# ProProject___2024-03-21.net
KiCad netlist of a schematic drawn in EasyEDA Pro
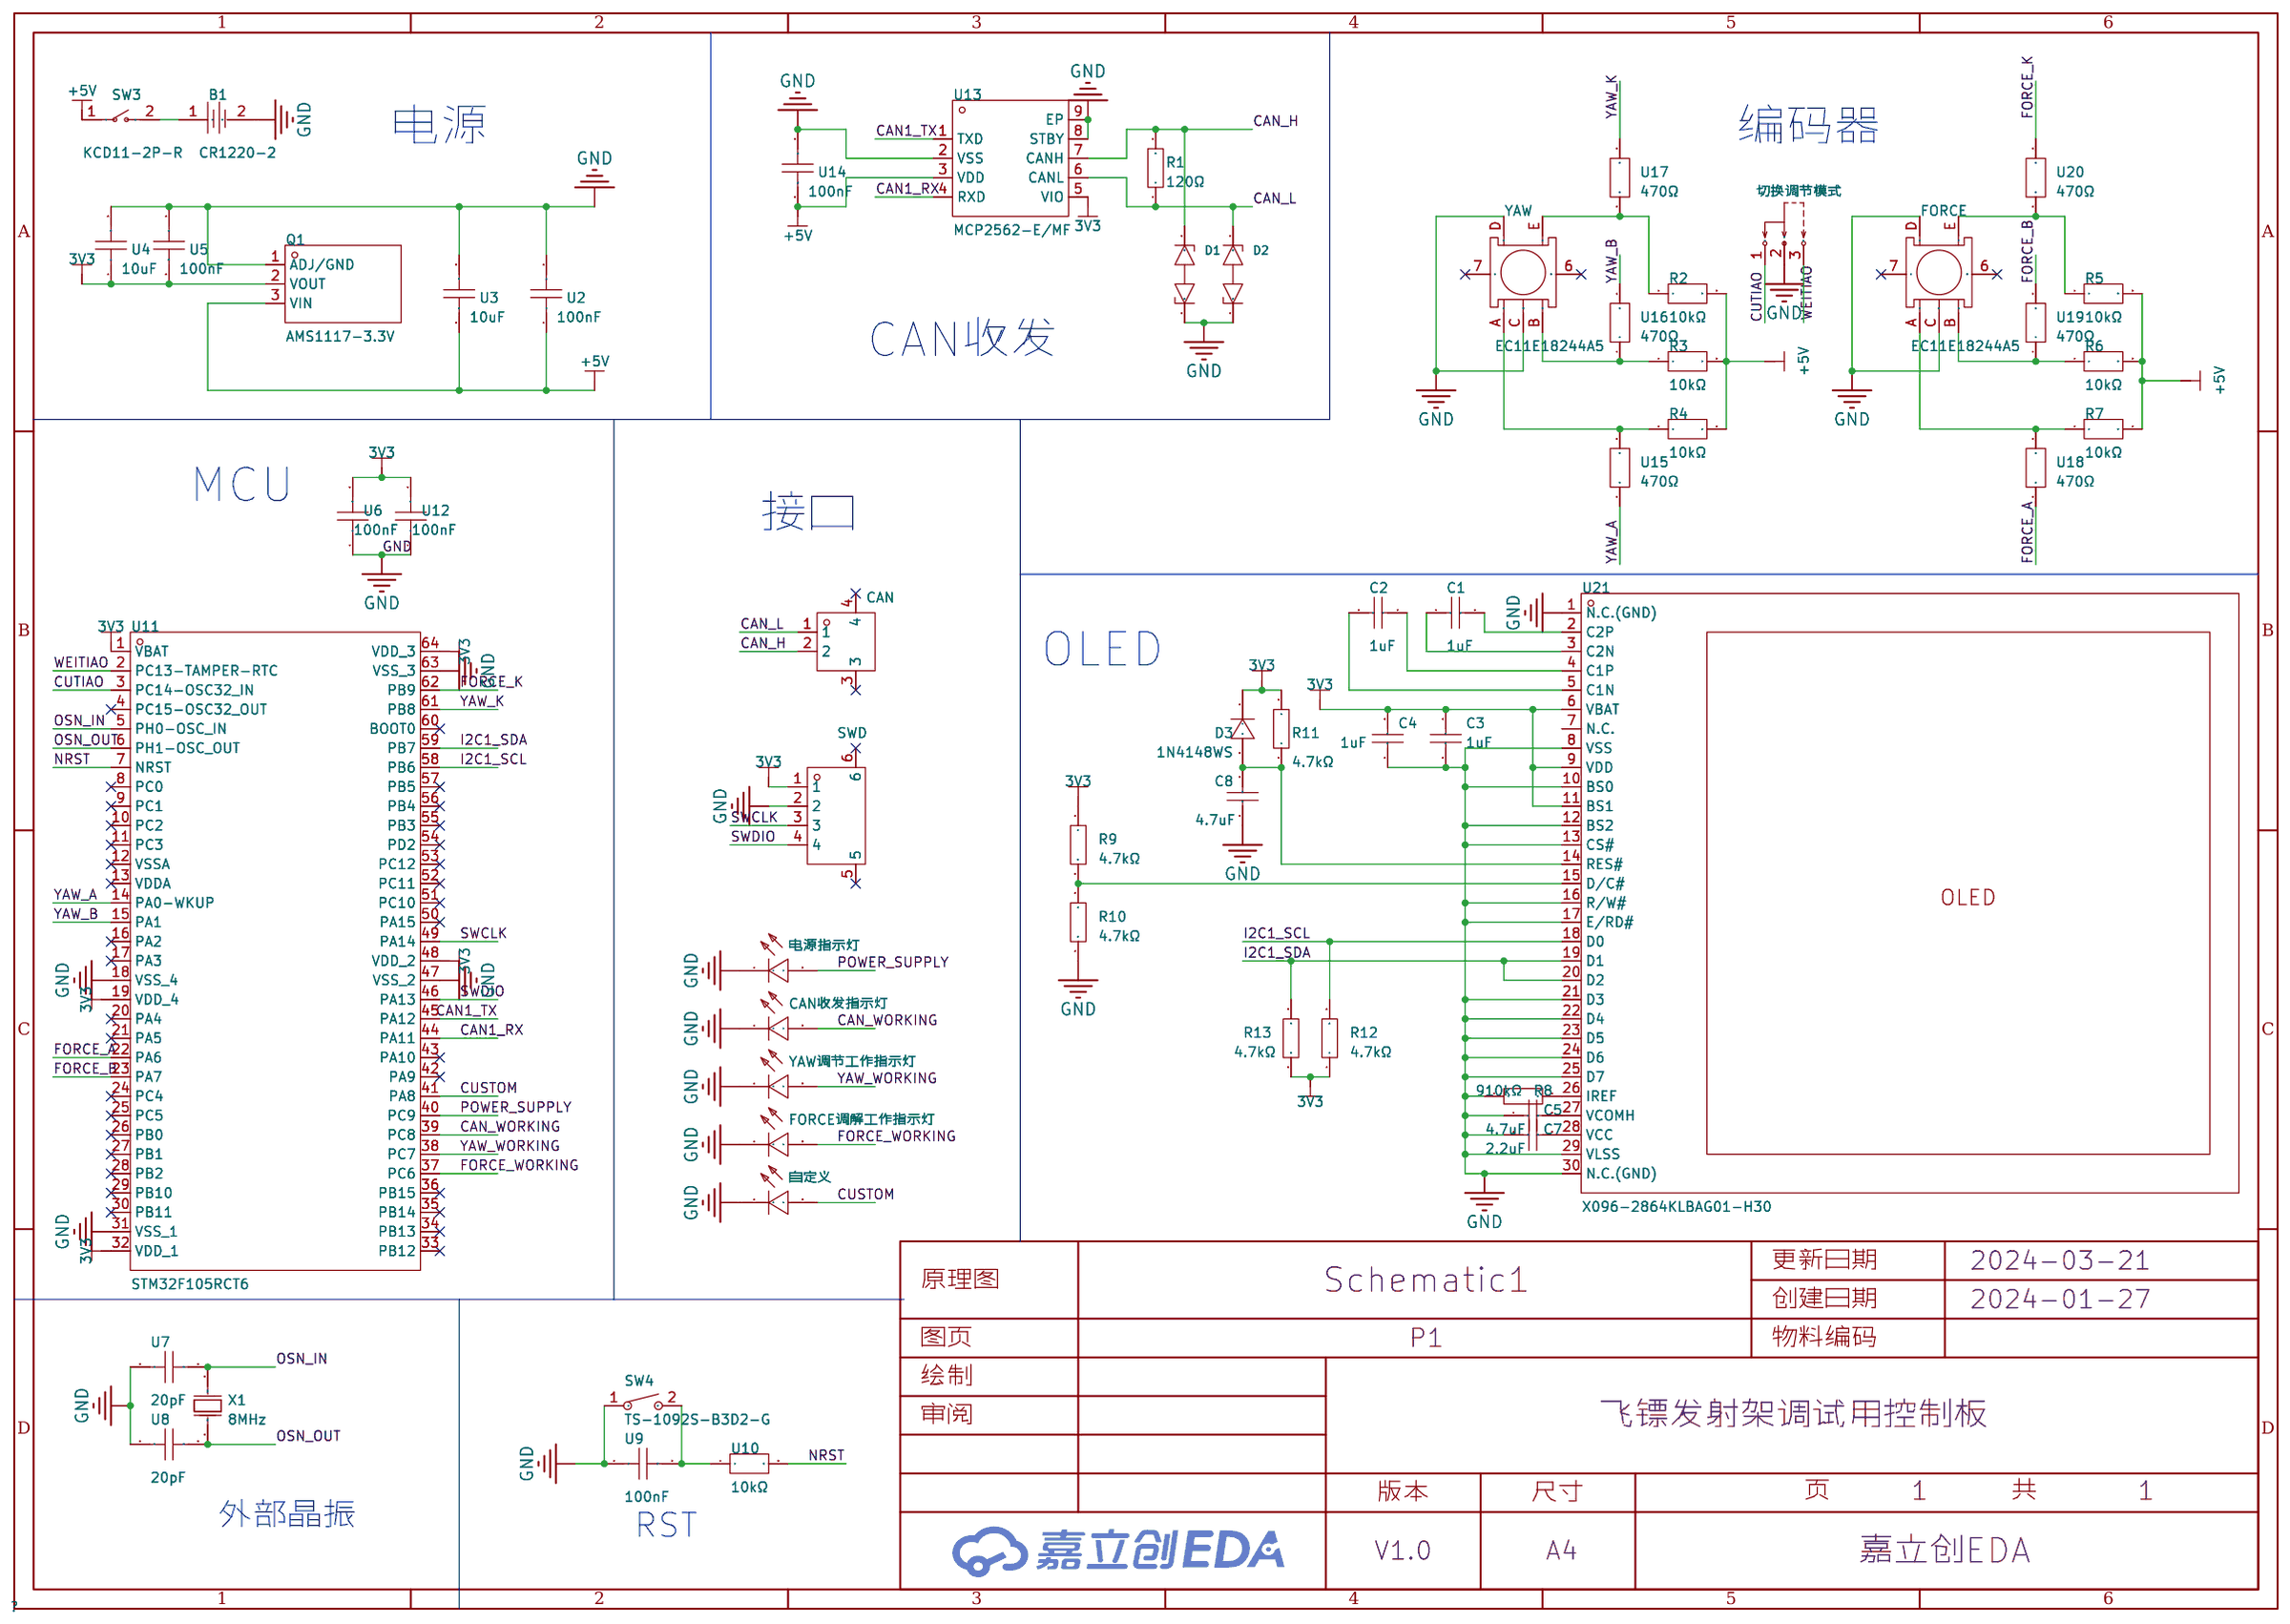
[diagram p0: schematic sheet]

(export (version "E")
  (design (tool "Eeschema 10.0.6"))
  (components
    (comp (ref "B1")
      (value "CR1220-2")
      (footprint "easyedapro:BAT-SMD_CR1220-2")
      (description "连接器类型:电池底座;适用电池规格:CR1220;工作温度范围:-;")
      (fields (field (name "Manufacturer") "Q&J"))
      (libsource (lib "easyedapro") (part "CR1220-2"))
    )
    (comp (ref "C1")
      (value "1uF")
      (footprint "easyedapro:C0603")
      (description "容值:1uF;精度:±10%;额定电压:25V;材质(温度系数):X7R;")
      (fields (field (name "Manufacturer Part") "0603B105K250NT") (field (name "Manufacturer") "FH(风华)"))
      (libsource (lib "easyedapro") (part "0603B105K250NT"))
    )
    (comp (ref "C2")
      (value "1uF")
      (footprint "easyedapro:C0603")
      (description "容值:1uF;精度:±10%;额定电压:25V;材质(温度系数):X7R;")
      (fields (field (name "Manufacturer Part") "0603B105K250NT") (field (name "Manufacturer") "FH(风华)"))
      (libsource (lib "easyedapro") (part "0603B105K250NT"))
    )
    (comp (ref "C3")
      (value "1uF")
      (footprint "easyedapro:C0603")
      (description "容值:1uF;精度:±10%;额定电压:25V;材质(温度系数):X7R;")
      (fields (field (name "Manufacturer Part") "0603B105K250NT") (field (name "Manufacturer") "FH(风华)"))
      (libsource (lib "easyedapro") (part "0603B105K250NT"))
    )
    (comp (ref "C4")
      (value "1uF")
      (footprint "easyedapro:C0603")
      (description "容值:1uF;精度:±10%;额定电压:25V;材质(温度系数):X7R;")
      (fields (field (name "Manufacturer Part") "0603B105K250NT") (field (name "Manufacturer") "FH(风华)"))
      (libsource (lib "easyedapro") (part "0603B105K250NT"))
    )
    (comp (ref "C5")
      (value "4.7uF")
      (footprint "easyedapro:C0603")
      (description "容值:4.7uF;精度:±10%;额定电压:16V;材质(温度系数):X5R;")
      (fields
        (field (name "Manufacturer Part") "CL10A475KO8NNNC")
        (field (name "Manufacturer") "SAMSUNG(三星)")
      )
      (libsource (lib "easyedapro") (part "CL10A475KO8NNNC"))
    )
    (comp (ref "C7")
      (value "2.2uF")
      (footprint "easyedapro:C0603")
      (description "容值:2.2uF;精度:±10%;额定电压:16V;材质(温度系数):X5R;")
      (fields
        (field (name "Manufacturer Part") "CL10A225KO8NNNC")
        (field (name "Manufacturer") "SAMSUNG(三星)")
      )
      (libsource (lib "easyedapro") (part "CL10A225KO8NNNC"))
    )
    (comp (ref "C8")
      (value "4.7uF")
      (footprint "easyedapro:C0603")
      (description "容值:4.7uF;精度:±10%;额定电压:16V;材质(温度系数):X5R;")
      (fields
        (field (name "Manufacturer Part") "CL10A475KO8NNNC")
        (field (name "Manufacturer") "SAMSUNG(三星)")
      )
      (libsource (lib "easyedapro") (part "CL10A475KO8NNNC"))
    )
    (comp (ref "CAN")
      (value "WAFER-GH1.25-2PLB")
      (footprint "easyedapro:CONN-TH_2P-P1.25_XUNPU_WAFER-GH1.25-2PLB")
      (description "插针结构:1x2P;间距:1.25mm;安装方式:立贴;参考系列:GH;总PIN数:2P;排数:1;每排PIN数:2;额定电流:1A;工作温度范围:-25°C~+85°C;")
      (fields (field (name "Manufacturer") "XUNPU(讯普)"))
      (libsource (lib "easyedapro") (part "WAFER-GH1.25-2PLB"))
    )
    (comp (ref "CAN收发指示灯")
      (value "NCD0603R1")
      (footprint "easyedapro:LED0603-RD_RED")
      (fields (field (name "Manufacturer") "国星光电"))
      (libsource (lib "easyedapro") (part "FC-DA1608HRK-620D"))
    )
    (comp (ref "D1")
      (value "PESD5V0S1BA,115")
      (footprint "easyedapro:SOD-323_L1.7-W1.3-LS2.5-BI")
      (description "极性:双向;反向截止电压(Vrwm):5V;最大钳位电压:14V;峰值脉冲电流(Ipp)@10/1000us:12A;峰值脉冲功率(Ppp)@10/1000us:130W;击穿电压:5.5V;")
      (fields (field (name "Manufacturer") "Nexperia(安世)"))
      (libsource (lib "easyedapro") (part "PESD5V0S1BA,115"))
    )
    (comp (ref "D2")
      (value "PESD5V0S1BA,115")
      (footprint "easyedapro:SOD-323_L1.7-W1.3-LS2.5-BI")
      (description "极性:双向;反向截止电压(Vrwm):5V;最大钳位电压:14V;峰值脉冲电流(Ipp)@10/1000us:12A;峰值脉冲功率(Ppp)@10/1000us:130W;击穿电压:5.5V;")
      (fields (field (name "Manufacturer") "Nexperia(安世)"))
      (libsource (lib "easyedapro") (part "PESD5V0S1BA,115"))
    )
    (comp (ref "D3")
      (value "1N4148WS")
      (footprint "easyedapro:SOD-323_L1.8-W1.3-LS2.5-RD")
      (description "二极管配置:独立式;正向压降(Vf):1.25V@150mA;直流反向耐压(Vr):100V;平均整流电流(Io):150mA;功率:200mW;反向恢复时间(trr):4ns;")
      (fields (field (name "Manufacturer") "CJ(江苏长电/长晶)"))
      (libsource (lib "easyedapro") (part "1N4148WS T4"))
    )
    (comp (ref "FORCE")
      (value "EC11E18244A5")
      (footprint "easyedapro:SW-TH_EC11E18244A5")
      (fields (field (name "Manufacturer") "ALPSALPINE(阿尔卑斯阿尔派)"))
      (libsource (lib "easyedapro") (part "EC11E18244A5"))
    )
    (comp (ref "FORCE调解工作指示灯")
      (value "NCD0603R1")
      (footprint "easyedapro:LED0603-RD_RED")
      (fields (field (name "Manufacturer") "国星光电"))
      (libsource (lib "easyedapro") (part "FC-DA1608HRK-620D"))
    )
    (comp (ref "Q1")
      (value "AMS1117-3.3V")
      (footprint "easyedapro:SOT-89-3_L4.5-W2.5-P1.50-LS4.2-BR")
      (description "输出类型:固定;最大输入电压:18V;输出电压:3.3V;最大输出电流:1A;输出极性:正极;")
      (fields (field (name "Manufacturer") "MSKSEMI(美森科)"))
      (libsource (lib "easyedapro") (part "AMS1117-3.3V_C5120796"))
    )
    (comp (ref "R1")
      (value "120Ω")
      (footprint "easyedapro:R0603")
      (description "电阻类型:厚膜电阻;阻值:120Ω;精度:±1%;功率:100mW;最大工作电压:75V;温度系数:±100ppm/°C;")
      (fields
        (field (name "Manufacturer Part") "0603WAF1200T5E")
        (field (name "Manufacturer") "UNI-ROYAL(厚声)")
      )
      (libsource (lib "easyedapro") (part "0603WAF1200T5E"))
    )
    (comp (ref "R2")
      (value "10kΩ")
      (footprint "easyedapro:R0603")
      (description "电阻类型:薄膜电阻;阻值:10kΩ;精度:±0.01%;功率:150mW;温度系数:±5ppm/°C;")
      (fields
        (field (name "Manufacturer Part") "PLT0603Z1002LBTS")
        (field (name "Manufacturer") "VISHAY(威世)")
      )
      (libsource (lib "easyedapro") (part "PLT0603Z1002LBTS"))
    )
    (comp (ref "R3")
      (value "10kΩ")
      (footprint "easyedapro:R0603")
      (description "电阻类型:薄膜电阻;阻值:10kΩ;精度:±0.01%;功率:150mW;温度系数:±5ppm/°C;")
      (fields
        (field (name "Manufacturer Part") "PLT0603Z1002LBTS")
        (field (name "Manufacturer") "VISHAY(威世)")
      )
      (libsource (lib "easyedapro") (part "PLT0603Z1002LBTS"))
    )
    (comp (ref "R4")
      (value "10kΩ")
      (footprint "easyedapro:R0603")
      (description "电阻类型:薄膜电阻;阻值:10kΩ;精度:±0.01%;功率:150mW;温度系数:±5ppm/°C;")
      (fields
        (field (name "Manufacturer Part") "PLT0603Z1002LBTS")
        (field (name "Manufacturer") "VISHAY(威世)")
      )
      (libsource (lib "easyedapro") (part "PLT0603Z1002LBTS"))
    )
    (comp (ref "R5")
      (value "10kΩ")
      (footprint "easyedapro:R0603")
      (description "电阻类型:薄膜电阻;阻值:10kΩ;精度:±0.01%;功率:150mW;温度系数:±5ppm/°C;")
      (fields
        (field (name "Manufacturer Part") "PLT0603Z1002LBTS")
        (field (name "Manufacturer") "VISHAY(威世)")
      )
      (libsource (lib "easyedapro") (part "PLT0603Z1002LBTS"))
    )
    (comp (ref "R6")
      (value "10kΩ")
      (footprint "easyedapro:R0603")
      (description "电阻类型:薄膜电阻;阻值:10kΩ;精度:±0.01%;功率:150mW;温度系数:±5ppm/°C;")
      (fields
        (field (name "Manufacturer Part") "PLT0603Z1002LBTS")
        (field (name "Manufacturer") "VISHAY(威世)")
      )
      (libsource (lib "easyedapro") (part "PLT0603Z1002LBTS"))
    )
    (comp (ref "R7")
      (value "10kΩ")
      (footprint "easyedapro:R0603")
      (description "电阻类型:薄膜电阻;阻值:10kΩ;精度:±0.01%;功率:150mW;温度系数:±5ppm/°C;")
      (fields
        (field (name "Manufacturer Part") "PLT0603Z1002LBTS")
        (field (name "Manufacturer") "VISHAY(威世)")
      )
      (libsource (lib "easyedapro") (part "PLT0603Z1002LBTS"))
    )
    (comp (ref "R8")
      (value "910kΩ")
      (footprint "easyedapro:R0603")
      (description "电阻类型:厚膜电阻;阻值:910kΩ;精度:±1%;功率:100mW;最大工作电压:75V;温度系数:±100ppm/°C;")
      (fields
        (field (name "Manufacturer Part") "0603WAF9103T5E")
        (field (name "Manufacturer") "UNI-ROYAL(厚声)")
      )
      (libsource (lib "easyedapro") (part "0603WAF9103T5E"))
    )
    (comp (ref "R9")
      (value "4.7kΩ")
      (footprint "easyedapro:R0603")
      (description "电阻类型:厚膜电阻;阻值:4.7kΩ;精度:±1%;功率:100mW;最大工作电压:75V;温度系数:±100ppm/°C;")
      (fields
        (field (name "Manufacturer Part") "0603WAF4701T5E")
        (field (name "Manufacturer") "UNI-ROYAL(厚声)")
      )
      (libsource (lib "easyedapro") (part "0603WAF4701T5E"))
    )
    (comp (ref "R10")
      (value "4.7kΩ")
      (footprint "easyedapro:R0603")
      (description "电阻类型:厚膜电阻;阻值:4.7kΩ;精度:±1%;功率:100mW;最大工作电压:75V;温度系数:±100ppm/°C;")
      (fields
        (field (name "Manufacturer Part") "0603WAF4701T5E")
        (field (name "Manufacturer") "UNI-ROYAL(厚声)")
      )
      (libsource (lib "easyedapro") (part "0603WAF4701T5E"))
    )
    (comp (ref "R11")
      (value "4.7kΩ")
      (footprint "easyedapro:R0603")
      (description "电阻类型:厚膜电阻;阻值:4.7kΩ;精度:±1%;功率:100mW;最大工作电压:75V;温度系数:±100ppm/°C;")
      (fields
        (field (name "Manufacturer Part") "0603WAF4701T5E")
        (field (name "Manufacturer") "UNI-ROYAL(厚声)")
      )
      (libsource (lib "easyedapro") (part "0603WAF4701T5E"))
    )
    (comp (ref "R12")
      (value "4.7kΩ")
      (footprint "easyedapro:R0603")
      (description "电阻类型:厚膜电阻;阻值:4.7kΩ;精度:±1%;功率:100mW;最大工作电压:75V;温度系数:±100ppm/°C;")
      (fields
        (field (name "Manufacturer Part") "0603WAF4701T5E")
        (field (name "Manufacturer") "UNI-ROYAL(厚声)")
      )
      (libsource (lib "easyedapro") (part "0603WAF4701T5E"))
    )
    (comp (ref "R13")
      (value "4.7kΩ")
      (footprint "easyedapro:R0603")
      (description "电阻类型:厚膜电阻;阻值:4.7kΩ;精度:±1%;功率:100mW;最大工作电压:75V;温度系数:±100ppm/°C;")
      (fields
        (field (name "Manufacturer Part") "0603WAF4701T5E")
        (field (name "Manufacturer") "UNI-ROYAL(厚声)")
      )
      (libsource (lib "easyedapro") (part "0603WAF4701T5E"))
    )
    (comp (ref "SW3")
      (value "KCD11-2P-R")
      (footprint "easyedapro:SW-TH_2P-L15.0-W10.5-P5.00_KCD11-2P-R")
      (description "带灯:无;引脚样式:焊片;额定电流:3A;额定电压(AC):250V;额定电压(DC):-;电路结构:单刀单掷;机械寿命:1万次;")
      (fields (field (name "Manufacturer") "SHOU HAN(首韩)"))
      (libsource (lib "easyedapro") (part "KCD11-2P-R"))
    )
    (comp (ref "SW4")
      (value "TS-1092S-B3D2-G")
      (footprint "easyedapro:SW-SMD_L6.1-W3.6-LS7.9")
      (description "电路结构:单刀单掷;按钮形状:矩形按钮;作用力:250gf;安装方式:立贴;开关长度:6.1mm;开关宽度:3.6mm;开关高度:2.5mm;带支架:不带;机械寿命:-;")
      (fields (field (name "Manufacturer") "Yuandi(元迪)"))
      (libsource (lib "easyedapro") (part "TS-1092S-B3D2-G"))
    )
    (comp (ref "SWD")
      (value "WAFER-MX1.25-4PWB")
      (footprint "easyedapro:CONN-SMD_4P-P1.25_WAFER-MX1.25-4PWB")
      (description "插针结构:1x4P;间距:1.25mm;安装方式:卧贴;总PIN数:4P;排数:1;每排PIN数:4;额定电流:1A;工作温度范围:-25°C~+85°C;")
      (fields (field (name "Manufacturer") "XUNPU(讯普)"))
      (libsource (lib "easyedapro") (part "WAFER-MX1.25-4PWB"))
    )
    (comp (ref "U2")
      (value "100nF")
      (footprint "easyedapro:C0603")
      (description "容值:100nF;精度:±20%;额定电压:16V;材质(温度系数):X7R;")
      (fields
        (field (name "Manufacturer Part") "EMK107B7104MA-T")
        (field (name "Manufacturer") "TAIYO YUDEN(太诱)")
      )
      (libsource (lib "easyedapro") (part "EMK107B7104MA-T"))
    )
    (comp (ref "U3")
      (value "10uF")
      (footprint "easyedapro:C0603")
      (description "容值:10uF;精度:±20%;额定电压:6.3V;材质(温度系数):X5R;")
      (fields
        (field (name "Manufacturer Part") "GRM188R60J106ME84D")
        (field (name "Manufacturer") "muRata(村田)")
      )
      (libsource (lib "easyedapro") (part "GRM188R60J106ME84D"))
    )
    (comp (ref "U4")
      (value "10uF")
      (footprint "easyedapro:C0603")
      (description "容值:10uF;精度:±20%;额定电压:6.3V;材质(温度系数):X5R;")
      (fields
        (field (name "Manufacturer Part") "GRM188R60J106ME84D")
        (field (name "Manufacturer") "muRata(村田)")
      )
      (libsource (lib "easyedapro") (part "GRM188R60J106ME84D"))
    )
    (comp (ref "U5")
      (value "100nF")
      (footprint "easyedapro:C0603")
      (description "容值:100nF;精度:±20%;额定电压:16V;材质(温度系数):X7R;")
      (fields
        (field (name "Manufacturer Part") "EMK107B7104MA-T")
        (field (name "Manufacturer") "TAIYO YUDEN(太诱)")
      )
      (libsource (lib "easyedapro") (part "EMK107B7104MA-T"))
    )
    (comp (ref "U6")
      (value "100nF")
      (footprint "easyedapro:C0603")
      (description "容值:100nF;精度:±20%;额定电压:16V;材质(温度系数):X7R;")
      (fields
        (field (name "Manufacturer Part") "EMK107B7104MA-T")
        (field (name "Manufacturer") "TAIYO YUDEN(太诱)")
      )
      (libsource (lib "easyedapro") (part "EMK107B7104MA-T"))
    )
    (comp (ref "U7")
      (value "20pF")
      (footprint "easyedapro:C0402")
      (description "容值:20pF;精度:±5%;额定电压:16V;材质(温度系数):C0G;")
      (fields (field (name "Manufacturer Part") "0402YA200JAT2A") (field (name "Manufacturer") "Kyocera AVX"))
      (libsource (lib "easyedapro") (part "0402YA200JAT2A"))
    )
    (comp (ref "U8")
      (value "20pF")
      (footprint "easyedapro:C0402")
      (description "容值:20pF;精度:±5%;额定电压:16V;材质(温度系数):C0G;")
      (fields (field (name "Manufacturer Part") "0402YA200JAT2A") (field (name "Manufacturer") "Kyocera AVX"))
      (libsource (lib "easyedapro") (part "0402YA200JAT2A"))
    )
    (comp (ref "U9")
      (value "100nF")
      (footprint "easyedapro:C0603")
      (description "容值:100nF;精度:±20%;额定电压:16V;材质(温度系数):X7R;")
      (fields
        (field (name "Manufacturer Part") "EMK107B7104MA-T")
        (field (name "Manufacturer") "TAIYO YUDEN(太诱)")
      )
      (libsource (lib "easyedapro") (part "EMK107B7104MA-T"))
    )
    (comp (ref "U10")
      (value "10kΩ")
      (footprint "easyedapro:R0603")
      (description "电阻类型:薄膜电阻;阻值:10kΩ;精度:±0.01%;功率:63mW;温度系数:±5ppm/°C;")
      (fields (field (name "Manufacturer Part") "APC0603T10K0Z") (field (name "Manufacturer") "Ohmite"))
      (libsource (lib "easyedapro") (part "APC0603T10K0Z"))
    )
    (comp (ref "U11")
      (value "STM32F105RCT6")
      (footprint "easyedapro:LQFP-64_L10.0-W10.0-P0.50-LS12.0-BL")
      (description "CPU内核:CM3;程序存储容量:256KB;RAM总容量:64KB;GPIO端口数量:51;工作电压范围:2V~3.6V;CPU最大主频:72MHz;程序存储器类型:FLASH;")
      (fields (field (name "Manufacturer") "ST(意法半导体)"))
      (libsource (lib "easyedapro") (part "STM32F105RCT6"))
    )
    (comp (ref "U12")
      (value "100nF")
      (footprint "easyedapro:C0603")
      (description "容值:100nF;精度:±20%;额定电压:16V;材质(温度系数):X7R;")
      (fields
        (field (name "Manufacturer Part") "EMK107B7104MA-T")
        (field (name "Manufacturer") "TAIYO YUDEN(太诱)")
      )
      (libsource (lib "easyedapro") (part "EMK107B7104MA-T"))
    )
    (comp (ref "U13")
      (value "MCP2562-E/MF")
      (footprint "easyedapro:DFN-8_L3.0-W3.0-P0.65-BL-EP")
      (description "类型:收发器;")
      (fields (field (name "Manufacturer") "MICROCHIP(美国微芯)"))
      (libsource (lib "easyedapro") (part "MCP2562-E/MF"))
    )
    (comp (ref "U14")
      (value "100nF")
      (footprint "easyedapro:C0603")
      (description "容值:100nF;精度:±20%;额定电压:16V;材质(温度系数):X7R;")
      (fields
        (field (name "Manufacturer Part") "EMK107B7104MA-T")
        (field (name "Manufacturer") "TAIYO YUDEN(太诱)")
      )
      (libsource (lib "easyedapro") (part "EMK107B7104MA-T"))
    )
    (comp (ref "U15")
      (value "470Ω")
      (footprint "easyedapro:R0603")
      (description "阻值:470Ω;精度:±5%;功率:-;温度系数:±100ppm/°C;")
      (fields
        (field (name "Manufacturer Part") "SC0603J4700F2BNRH")
        (field (name "Manufacturer") "Sunway(信维通信)")
      )
      (libsource (lib "easyedapro") (part "SC0603J4700F2BNRH"))
    )
    (comp (ref "U16")
      (value "470Ω")
      (footprint "easyedapro:R0603")
      (description "阻值:470Ω;精度:±5%;功率:-;温度系数:±100ppm/°C;")
      (fields
        (field (name "Manufacturer Part") "SC0603J4700F2BNRH")
        (field (name "Manufacturer") "Sunway(信维通信)")
      )
      (libsource (lib "easyedapro") (part "SC0603J4700F2BNRH"))
    )
    (comp (ref "U17")
      (value "470Ω")
      (footprint "easyedapro:R0603")
      (description "阻值:470Ω;精度:±5%;功率:-;温度系数:±100ppm/°C;")
      (fields
        (field (name "Manufacturer Part") "SC0603J4700F2BNRH")
        (field (name "Manufacturer") "Sunway(信维通信)")
      )
      (libsource (lib "easyedapro") (part "SC0603J4700F2BNRH"))
    )
    (comp (ref "U18")
      (value "470Ω")
      (footprint "easyedapro:R0603")
      (description "阻值:470Ω;精度:±5%;功率:-;温度系数:±100ppm/°C;")
      (fields
        (field (name "Manufacturer Part") "SC0603J4700F2BNRH")
        (field (name "Manufacturer") "Sunway(信维通信)")
      )
      (libsource (lib "easyedapro") (part "SC0603J4700F2BNRH"))
    )
    (comp (ref "U19")
      (value "470Ω")
      (footprint "easyedapro:R0603")
      (description "阻值:470Ω;精度:±5%;功率:-;温度系数:±100ppm/°C;")
      (fields
        (field (name "Manufacturer Part") "SC0603J4700F2BNRH")
        (field (name "Manufacturer") "Sunway(信维通信)")
      )
      (libsource (lib "easyedapro") (part "SC0603J4700F2BNRH"))
    )
    (comp (ref "U20")
      (value "470Ω")
      (footprint "easyedapro:R0603")
      (description "阻值:470Ω;精度:±5%;功率:-;温度系数:±100ppm/°C;")
      (fields
        (field (name "Manufacturer Part") "SC0603J4700F2BNRH")
        (field (name "Manufacturer") "Sunway(信维通信)")
      )
      (libsource (lib "easyedapro") (part "SC0603J4700F2BNRH"))
    )
    (comp (ref "U21")
      (value "X096-2864KLBAG01-H30")
      (footprint "easyedapro:OLED-SMD_X096-2864KLBAG01-H30")
      (description "主控芯片:SSD1315;尺寸(inch):0.96;像素分辨率:128x64;")
      (fields (field (name "Manufacturer") "Newvision(新智景)"))
      (libsource (lib "easyedapro") (part "X096-2864KLBAG01-H30"))
    )
    (comp (ref "X1")
      (value "8MHz")
      (footprint "easyedapro:CRYSTAL-SMD_L5.0-W3.2")
      (description "晶振类型:贴片晶振;频率:8MHz;常温频差:±10ppm;外接负载电容:20pF;频率稳定度(全温):±50ppm;")
      (fields (field (name "Manufacturer Part") "X50328MSB2GI") (field (name "Manufacturer") "YXC(扬兴晶振)"))
      (libsource (lib "easyedapro") (part "X50328MSB2GI"))
    )
    (comp (ref "YAW")
      (value "EC11E18244A5")
      (footprint "easyedapro:SW-TH_EC11E18244A5")
      (fields (field (name "Manufacturer") "ALPSALPINE(阿尔卑斯阿尔派)"))
      (libsource (lib "easyedapro") (part "EC11E18244A5"))
    )
    (comp (ref "YAW调节工作指示灯")
      (value "NCD0603R1")
      (footprint "easyedapro:LED0603-RD_RED")
      (fields (field (name "Manufacturer") "国星光电"))
      (libsource (lib "easyedapro") (part "FC-DA1608HRK-620D"))
    )
    (comp (ref "切换调节模式")
      (value "SS12D10G5")
      (footprint "easyedapro:SW-TH_SHOU-HAN_SS12D10G4")
      (description "电路结构:单刀双掷;安装方式:直插;额定电流(DC):2A;额定电压(DC):125V;机械寿命:3千次;")
      (fields (field (name "Manufacturer") "SHOU HAN(首韩)"))
      (libsource (lib "easyedapro") (part "SS12D10G5"))
    )
    (comp (ref "电源指示灯")
      (value "NCD0603R1")
      (footprint "easyedapro:LED0603-RD_RED")
      (fields (field (name "Manufacturer") "国星光电"))
      (libsource (lib "easyedapro") (part "FC-DA1608HRK-620D"))
    )
    (comp (ref "自定义")
      (value "NCD0603R1")
      (footprint "easyedapro:LED0603-RD_RED")
      (fields (field (name "Manufacturer") "国星光电"))
      (libsource (lib "easyedapro") (part "FC-DA1608HRK-620D"))
    )
  )
  (nets
    (net (code "1") (name "+5V") (class "Default")
      (node (ref "Q1") (pin "3") (pinfunction "VIN_3") (pintype "unspecified"))
      (node (ref "R2") (pin "2") (pinfunction "2_2") (pintype "unspecified"))
      (node (ref "R3") (pin "2") (pinfunction "2_2") (pintype "unspecified"))
      (node (ref "R4") (pin "2") (pinfunction "2_2") (pintype "unspecified"))
      (node (ref "R5") (pin "2") (pinfunction "2_2") (pintype "unspecified"))
      (node (ref "R6") (pin "2") (pinfunction "2_2") (pintype "unspecified"))
      (node (ref "R7") (pin "2") (pinfunction "2_2") (pintype "unspecified"))
      (node (ref "SW3") (pin "1") (pinfunction "1_1") (pintype "unspecified"))
      (node (ref "U13") (pin "3") (pinfunction "VDD_3") (pintype "input"))
      (node (ref "U14") (pin "1") (pinfunction "1_1") (pintype "unspecified"))
      (node (ref "U2") (pin "1") (pinfunction "1_1") (pintype "unspecified"))
      (node (ref "U3") (pin "1") (pinfunction "1_1") (pintype "unspecified"))
    )
    (net (code "2") (name "/CAN1_RX") (class "Default")
      (node (ref "U11") (pin "44") (pinfunction "PA11_44") (pintype "unspecified"))
      (node (ref "U13") (pin "4") (pinfunction "RXD_4") (pintype "input"))
    )
    (net (code "3") (name "/CAN1_TX") (class "Default")
      (node (ref "U11") (pin "45") (pinfunction "PA12_45") (pintype "unspecified"))
      (node (ref "U13") (pin "1") (pinfunction "TXD_1") (pintype "input"))
    )
    (net (code "4") (name "/CAN_H") (class "Default")
      (node (ref "CAN") (pin "2") (pinfunction "2_2") (pintype "unspecified"))
      (node (ref "D1") (pin "2") (pinfunction "2_2") (pintype "input"))
      (node (ref "R1") (pin "2") (pinfunction "2_2") (pintype "input"))
      (node (ref "U13") (pin "7") (pinfunction "CANH_7") (pintype "input"))
    )
    (net (code "5") (name "/CAN_L") (class "Default")
      (node (ref "CAN") (pin "1") (pinfunction "1_1") (pintype "unspecified"))
      (node (ref "D2") (pin "2") (pinfunction "2_2") (pintype "input"))
      (node (ref "R1") (pin "1") (pinfunction "1_1") (pintype "input"))
      (node (ref "U13") (pin "6") (pinfunction "CANL_6") (pintype "input"))
    )
    (net (code "6") (name "/CAN_WORKING") (class "Default")
      (node (ref "CAN收发指示灯") (pin "2") (pinfunction "A_2") (pintype "input"))
      (node (ref "U11") (pin "39") (pinfunction "PC8_39") (pintype "unspecified"))
    )
    (net (code "7") (name "/CUSTOM") (class "Default")
      (node (ref "U11") (pin "41") (pinfunction "PA8_41") (pintype "unspecified"))
      (node (ref "自定义") (pin "2") (pinfunction "A_2") (pintype "input"))
    )
    (net (code "8") (name "/CUTIAO") (class "Default")
      (node (ref "U11") (pin "3") (pinfunction "PC14-OSC32_IN_3") (pintype "unspecified"))
      (node (ref "切换调节模式") (pin "1") (pinfunction "1_1") (pintype "unspecified"))
    )
    (net (code "9") (name "/FORCE_A") (class "Default")
      (node (ref "U11") (pin "22") (pinfunction "PA6_22") (pintype "unspecified"))
      (node (ref "U18") (pin "1") (pinfunction "1_1") (pintype "unspecified"))
    )
    (net (code "10") (name "/FORCE_B") (class "Default")
      (node (ref "U11") (pin "23") (pinfunction "PA7_23") (pintype "unspecified"))
      (node (ref "U19") (pin "2") (pinfunction "2_2") (pintype "unspecified"))
    )
    (net (code "11") (name "/FORCE_K") (class "Default")
      (node (ref "U11") (pin "62") (pinfunction "PB9_62") (pintype "unspecified"))
      (node (ref "U20") (pin "2") (pinfunction "2_2") (pintype "unspecified"))
    )
    (net (code "12") (name "/FORCE_WORKING") (class "Default")
      (node (ref "FORCE调解工作指示灯") (pin "2") (pinfunction "A_2") (pintype "input"))
      (node (ref "U11") (pin "37") (pinfunction "PC6_37") (pintype "unspecified"))
    )
    (net (code "13") (name "/I2C1_SCL") (class "Default")
      (node (ref "R12") (pin "2") (pinfunction "2_2") (pintype "input"))
      (node (ref "U11") (pin "58") (pinfunction "PB6_58") (pintype "unspecified"))
      (node (ref "U21") (pin "18") (pinfunction "D0_18") (pintype "unspecified"))
    )
    (net (code "14") (name "/I2C1_SDA") (class "Default")
      (node (ref "R13") (pin "2") (pinfunction "2_2") (pintype "input"))
      (node (ref "U11") (pin "59") (pinfunction "PB7_59") (pintype "unspecified"))
      (node (ref "U21") (pin "19") (pinfunction "D1_19") (pintype "unspecified"))
      (node (ref "U21") (pin "20") (pinfunction "D2_20") (pintype "unspecified"))
    )
    (net (code "15") (name "/NRST") (class "Default")
      (node (ref "U10") (pin "2") (pinfunction "2_2") (pintype "unspecified"))
      (node (ref "U11") (pin "7") (pinfunction "NRST_7") (pintype "unspecified"))
    )
    (net (code "16") (name "/OSN_IN") (class "Default")
      (node (ref "U11") (pin "5") (pinfunction "PH0-OSC_IN_5") (pintype "unspecified"))
      (node (ref "U7") (pin "2") (pinfunction "2_2") (pintype "unspecified"))
      (node (ref "X1") (pin "2") (pinfunction "OSC2_2") (pintype "input"))
    )
    (net (code "17") (name "/OSN_OUT") (class "Default")
      (node (ref "U11") (pin "6") (pinfunction "PH1-OSC_OUT_6") (pintype "unspecified"))
      (node (ref "U8") (pin "2") (pinfunction "2_2") (pintype "unspecified"))
      (node (ref "X1") (pin "1") (pinfunction "OSC1_1") (pintype "input"))
    )
    (net (code "18") (name "/POWER_SUPPLY") (class "Default")
      (node (ref "U11") (pin "40") (pinfunction "PC9_40") (pintype "unspecified"))
      (node (ref "电源指示灯") (pin "2") (pinfunction "A_2") (pintype "input"))
    )
    (net (code "19") (name "/SWCLK") (class "Default")
      (node (ref "SWD") (pin "3") (pinfunction "3_3") (pintype "unspecified"))
      (node (ref "U11") (pin "49") (pinfunction "PA14_49") (pintype "unspecified"))
    )
    (net (code "20") (name "/SWDIO") (class "Default")
      (node (ref "SWD") (pin "4") (pinfunction "4_4") (pintype "unspecified"))
      (node (ref "U11") (pin "46") (pinfunction "PA13_46") (pintype "unspecified"))
    )
    (net (code "21") (name "/WEITIAO") (class "Default")
      (node (ref "U11") (pin "2") (pinfunction "PC13-TAMPER-RTC_2") (pintype "unspecified"))
      (node (ref "切换调节模式") (pin "3") (pinfunction "3_3") (pintype "unspecified"))
    )
    (net (code "22") (name "/YAW_A") (class "Default")
      (node (ref "U11") (pin "14") (pinfunction "PA0-WKUP_14") (pintype "unspecified"))
      (node (ref "U15") (pin "1") (pinfunction "1_1") (pintype "unspecified"))
    )
    (net (code "23") (name "/YAW_B") (class "Default")
      (node (ref "U11") (pin "15") (pinfunction "PA1_15") (pintype "unspecified"))
      (node (ref "U16") (pin "2") (pinfunction "2_2") (pintype "unspecified"))
    )
    (net (code "24") (name "/YAW_K") (class "Default")
      (node (ref "U11") (pin "61") (pinfunction "PB8_61") (pintype "unspecified"))
      (node (ref "U17") (pin "2") (pinfunction "2_2") (pintype "unspecified"))
    )
    (net (code "25") (name "/YAW_WORKING") (class "Default")
      (node (ref "U11") (pin "38") (pinfunction "PC7_38") (pintype "unspecified"))
      (node (ref "YAW调节工作指示灯") (pin "2") (pinfunction "A_2") (pintype "input"))
    )
    (net (code "26") (name "3V3") (class "Default")
      (node (ref "C3") (pin "2") (pinfunction "2_2") (pintype "input"))
      (node (ref "C4") (pin "2") (pinfunction "2_2") (pintype "input"))
      (node (ref "D3") (pin "1") (pinfunction "K_1") (pintype "unspecified"))
      (node (ref "Q1") (pin "2") (pinfunction "VOUT_2") (pintype "unspecified"))
      (node (ref "R11") (pin "2") (pinfunction "2_2") (pintype "input"))
      (node (ref "R12") (pin "1") (pinfunction "1_1") (pintype "input"))
      (node (ref "R13") (pin "1") (pinfunction "1_1") (pintype "input"))
      (node (ref "R9") (pin "1") (pinfunction "1_1") (pintype "input"))
      (node (ref "SWD") (pin "1") (pinfunction "1_1") (pintype "unspecified"))
      (node (ref "U11") (pin "1") (pinfunction "VBAT_1") (pintype "unspecified"))
      (node (ref "U11") (pin "19") (pinfunction "VDD_4_19") (pintype "unspecified"))
      (node (ref "U11") (pin "32") (pinfunction "VDD_1_32") (pintype "unspecified"))
      (node (ref "U11") (pin "48") (pinfunction "VDD_2_48") (pintype "unspecified"))
      (node (ref "U11") (pin "64") (pinfunction "VDD_3_64") (pintype "unspecified"))
      (node (ref "U12") (pin "2") (pinfunction "2_2") (pintype "unspecified"))
      (node (ref "U13") (pin "5") (pinfunction "VIO_5") (pintype "input"))
      (node (ref "U21") (pin "11") (pinfunction "BS1_11") (pintype "unspecified"))
      (node (ref "U21") (pin "6") (pinfunction "VBAT_6") (pintype "unspecified"))
      (node (ref "U21") (pin "9") (pinfunction "VDD_9") (pintype "unspecified"))
      (node (ref "U4") (pin "1") (pinfunction "1_1") (pintype "unspecified"))
      (node (ref "U5") (pin "2") (pinfunction "2_2") (pintype "unspecified"))
      (node (ref "U6") (pin "2") (pinfunction "2_2") (pintype "unspecified"))
    )
    (net (code "27") (name "GND") (class "Default")
      (node (ref "B1") (pin "2") (pinfunction "2_2") (pintype "input"))
      (node (ref "C3") (pin "1") (pinfunction "1_1") (pintype "input"))
      (node (ref "C4") (pin "1") (pinfunction "1_1") (pintype "input"))
      (node (ref "C5") (pin "1") (pinfunction "1_1") (pintype "input"))
      (node (ref "C7") (pin "1") (pinfunction "1_1") (pintype "input"))
      (node (ref "C8") (pin "1") (pinfunction "1_1") (pintype "input"))
      (node (ref "CAN收发指示灯") (pin "1") (pinfunction "K_1") (pintype "input"))
      (node (ref "D1") (pin "1") (pinfunction "1_1") (pintype "input"))
      (node (ref "D2") (pin "1") (pinfunction "1_1") (pintype "input"))
      (node (ref "FORCE") (pin "C") (pinfunction "C_C") (pintype "unspecified"))
      (node (ref "FORCE") (pin "D") (pinfunction "D_D") (pintype "unspecified"))
      (node (ref "FORCE调解工作指示灯") (pin "1") (pinfunction "K_1") (pintype "input"))
      (node (ref "Q1") (pin "1") (pinfunction "ADJ/GND_1") (pintype "unspecified"))
      (node (ref "R10") (pin "1") (pinfunction "1_1") (pintype "input"))
      (node (ref "R8") (pin "1") (pinfunction "1_1") (pintype "input"))
      (node (ref "SW4") (pin "1") (pinfunction "1_1") (pintype "unspecified"))
      (node (ref "SWD") (pin "2") (pinfunction "2_2") (pintype "unspecified"))
      (node (ref "U11") (pin "18") (pinfunction "VSS_4_18") (pintype "unspecified"))
      (node (ref "U11") (pin "31") (pinfunction "VSS_1_31") (pintype "unspecified"))
      (node (ref "U11") (pin "47") (pinfunction "VSS_2_47") (pintype "unspecified"))
      (node (ref "U11") (pin "63") (pinfunction "VSS_3_63") (pintype "unspecified"))
      (node (ref "U12") (pin "1") (pinfunction "1_1") (pintype "unspecified"))
      (node (ref "U13") (pin "2") (pinfunction "VSS_2") (pintype "input"))
      (node (ref "U13") (pin "8") (pinfunction "STBY_8") (pintype "input"))
      (node (ref "U13") (pin "9") (pinfunction "EP_9") (pintype "input"))
      (node (ref "U14") (pin "2") (pinfunction "2_2") (pintype "unspecified"))
      (node (ref "U2") (pin "2") (pinfunction "2_2") (pintype "unspecified"))
      (node (ref "U21") (pin "1") (pinfunction "N.C.(GND)_1") (pintype "unspecified"))
      (node (ref "U21") (pin "10") (pinfunction "BS0_10") (pintype "unspecified"))
      (node (ref "U21") (pin "12") (pinfunction "BS2_12") (pintype "unspecified"))
      (node (ref "U21") (pin "13") (pinfunction "CS#_13") (pintype "unspecified"))
      (node (ref "U21") (pin "16") (pinfunction "R/W#_16") (pintype "unspecified"))
      (node (ref "U21") (pin "17") (pinfunction "E/RD#_17") (pintype "unspecified"))
      (node (ref "U21") (pin "21") (pinfunction "D3_21") (pintype "unspecified"))
      (node (ref "U21") (pin "22") (pinfunction "D4_22") (pintype "unspecified"))
      (node (ref "U21") (pin "23") (pinfunction "D5_23") (pintype "unspecified"))
      (node (ref "U21") (pin "24") (pinfunction "D6_24") (pintype "unspecified"))
      (node (ref "U21") (pin "25") (pinfunction "D7_25") (pintype "unspecified"))
      (node (ref "U21") (pin "29") (pinfunction "VLSS_29") (pintype "unspecified"))
      (node (ref "U21") (pin "30") (pinfunction "N.C.(GND)_30") (pintype "unspecified"))
      (node (ref "U21") (pin "8") (pinfunction "VSS_8") (pintype "unspecified"))
      (node (ref "U3") (pin "2") (pinfunction "2_2") (pintype "unspecified"))
      (node (ref "U4") (pin "2") (pinfunction "2_2") (pintype "unspecified"))
      (node (ref "U5") (pin "1") (pinfunction "1_1") (pintype "unspecified"))
      (node (ref "U6") (pin "1") (pinfunction "1_1") (pintype "unspecified"))
      (node (ref "U7") (pin "1") (pinfunction "1_1") (pintype "unspecified"))
      (node (ref "U8") (pin "1") (pinfunction "1_1") (pintype "unspecified"))
      (node (ref "U9") (pin "1") (pinfunction "1_1") (pintype "unspecified"))
      (node (ref "YAW") (pin "C") (pinfunction "C_C") (pintype "unspecified"))
      (node (ref "YAW") (pin "D") (pinfunction "D_D") (pintype "unspecified"))
      (node (ref "YAW调节工作指示灯") (pin "1") (pinfunction "K_1") (pintype "input"))
      (node (ref "切换调节模式") (pin "2") (pinfunction "2_2") (pintype "unspecified"))
      (node (ref "电源指示灯") (pin "1") (pinfunction "K_1") (pintype "input"))
      (node (ref "自定义") (pin "1") (pinfunction "K_1") (pintype "input"))
    )
    (net (code "28") (name "Net-(B1-Pad1)") (class "Default")
      (node (ref "B1") (pin "1") (pinfunction "1_1") (pintype "input"))
      (node (ref "SW3") (pin "2") (pinfunction "2_2") (pintype "unspecified"))
    )
    (net (code "29") (name "Net-(D3-A)") (class "Default")
      (node (ref "C8") (pin "2") (pinfunction "2_2") (pintype "input"))
      (node (ref "D3") (pin "2") (pinfunction "A_2") (pintype "unspecified"))
      (node (ref "R11") (pin "1") (pinfunction "1_1") (pintype "input"))
      (node (ref "U21") (pin "14") (pinfunction "RES#_14") (pintype "unspecified"))
    )
    (net (code "30") (name "Net-(FORCE-PadA)") (class "Default")
      (node (ref "FORCE") (pin "A") (pinfunction "A_A") (pintype "unspecified"))
      (node (ref "R7") (pin "1") (pinfunction "1_1") (pintype "unspecified"))
      (node (ref "U18") (pin "2") (pinfunction "2_2") (pintype "unspecified"))
    )
    (net (code "31") (name "Net-(FORCE-PadB)") (class "Default")
      (node (ref "FORCE") (pin "B") (pinfunction "B_B") (pintype "unspecified"))
      (node (ref "R6") (pin "1") (pinfunction "1_1") (pintype "unspecified"))
      (node (ref "U19") (pin "1") (pinfunction "1_1") (pintype "unspecified"))
    )
    (net (code "32") (name "Net-(FORCE-PadE)") (class "Default")
      (node (ref "FORCE") (pin "E") (pinfunction "E_E") (pintype "unspecified"))
      (node (ref "R5") (pin "1") (pinfunction "1_1") (pintype "unspecified"))
      (node (ref "U20") (pin "1") (pinfunction "1_1") (pintype "unspecified"))
    )
    (net (code "33") (name "Net-(R2-Pad1)") (class "Default")
      (node (ref "R2") (pin "1") (pinfunction "1_1") (pintype "unspecified"))
      (node (ref "U17") (pin "1") (pinfunction "1_1") (pintype "unspecified"))
      (node (ref "YAW") (pin "E") (pinfunction "E_E") (pintype "unspecified"))
    )
    (net (code "34") (name "Net-(R3-Pad1)") (class "Default")
      (node (ref "R3") (pin "1") (pinfunction "1_1") (pintype "unspecified"))
      (node (ref "U16") (pin "1") (pinfunction "1_1") (pintype "unspecified"))
      (node (ref "YAW") (pin "B") (pinfunction "B_B") (pintype "unspecified"))
    )
    (net (code "35") (name "Net-(R4-Pad1)") (class "Default")
      (node (ref "R4") (pin "1") (pinfunction "1_1") (pintype "unspecified"))
      (node (ref "U15") (pin "2") (pinfunction "2_2") (pintype "unspecified"))
      (node (ref "YAW") (pin "A") (pinfunction "A_A") (pintype "unspecified"))
    )
    (net (code "36") (name "Net-(SW4-Pad2)") (class "Default")
      (node (ref "SW4") (pin "2") (pinfunction "2_2") (pintype "unspecified"))
      (node (ref "U10") (pin "1") (pinfunction "1_1") (pintype "unspecified"))
      (node (ref "U9") (pin "2") (pinfunction "2_2") (pintype "unspecified"))
    )
    (net (code "37") (name "Net-(U21-C1N)") (class "Default")
      (node (ref "C2") (pin "1") (pinfunction "1_1") (pintype "input"))
      (node (ref "U21") (pin "5") (pinfunction "C1N_5") (pintype "unspecified"))
    )
    (net (code "38") (name "Net-(U21-C1P)") (class "Default")
      (node (ref "C2") (pin "2") (pinfunction "2_2") (pintype "input"))
      (node (ref "U21") (pin "4") (pinfunction "C1P_4") (pintype "unspecified"))
    )
    (net (code "39") (name "Net-(U21-C2N)") (class "Default")
      (node (ref "C1") (pin "1") (pinfunction "1_1") (pintype "input"))
      (node (ref "U21") (pin "3") (pinfunction "C2N_3") (pintype "unspecified"))
    )
    (net (code "40") (name "Net-(U21-C2P)") (class "Default")
      (node (ref "C1") (pin "2") (pinfunction "2_2") (pintype "input"))
      (node (ref "U21") (pin "2") (pinfunction "C2P_2") (pintype "unspecified"))
    )
    (net (code "41") (name "Net-(U21-D{slash}C#)") (class "Default")
      (node (ref "R10") (pin "2") (pinfunction "2_2") (pintype "input"))
      (node (ref "R9") (pin "2") (pinfunction "2_2") (pintype "input"))
      (node (ref "U21") (pin "15") (pinfunction "D/C#_15") (pintype "unspecified"))
    )
    (net (code "42") (name "Net-(U21-IREF)") (class "Default")
      (node (ref "R8") (pin "2") (pinfunction "2_2") (pintype "input"))
      (node (ref "U21") (pin "26") (pinfunction "IREF_26") (pintype "unspecified"))
    )
    (net (code "43") (name "Net-(U21-VCC)") (class "Default")
      (node (ref "C7") (pin "2") (pinfunction "2_2") (pintype "input"))
      (node (ref "U21") (pin "28") (pinfunction "VCC_28") (pintype "unspecified"))
    )
    (net (code "44") (name "Net-(U21-VCOMH)") (class "Default")
      (node (ref "C5") (pin "2") (pinfunction "2_2") (pintype "input"))
      (node (ref "U21") (pin "27") (pinfunction "VCOMH_27") (pintype "unspecified"))
    )
    (net (code "45") (name "unconnected-(CAN-Pad3)") (class "Default")
      (node (ref "CAN") (pin "3") (pinfunction "3_3") (pintype "unspecified+no_connect"))
    )
    (net (code "46") (name "unconnected-(CAN-Pad4)") (class "Default")
      (node (ref "CAN") (pin "4") (pinfunction "4_4") (pintype "unspecified+no_connect"))
    )
    (net (code "47") (name "unconnected-(FORCE-Pad6)") (class "Default")
      (node (ref "FORCE") (pin "6") (pinfunction "6_6") (pintype "unspecified+no_connect"))
    )
    (net (code "48") (name "unconnected-(FORCE-Pad7)") (class "Default")
      (node (ref "FORCE") (pin "7") (pinfunction "7_7") (pintype "unspecified+no_connect"))
    )
    (net (code "49") (name "unconnected-(SWD-Pad5)") (class "Default")
      (node (ref "SWD") (pin "5") (pinfunction "5_5") (pintype "unspecified+no_connect"))
    )
    (net (code "50") (name "unconnected-(SWD-Pad6)") (class "Default")
      (node (ref "SWD") (pin "6") (pinfunction "6_6") (pintype "unspecified+no_connect"))
    )
    (net (code "51") (name "unconnected-(U11-BOOT0-Pad60)") (class "Default")
      (node (ref "U11") (pin "60") (pinfunction "BOOT0_60") (pintype "unspecified+no_connect"))
    )
    (net (code "52") (name "unconnected-(U11-PA2-Pad16)") (class "Default")
      (node (ref "U11") (pin "16") (pinfunction "PA2_16") (pintype "unspecified+no_connect"))
    )
    (net (code "53") (name "unconnected-(U11-PA3-Pad17)") (class "Default")
      (node (ref "U11") (pin "17") (pinfunction "PA3_17") (pintype "unspecified+no_connect"))
    )
    (net (code "54") (name "unconnected-(U11-PA4-Pad20)") (class "Default")
      (node (ref "U11") (pin "20") (pinfunction "PA4_20") (pintype "unspecified+no_connect"))
    )
    (net (code "55") (name "unconnected-(U11-PA5-Pad21)") (class "Default")
      (node (ref "U11") (pin "21") (pinfunction "PA5_21") (pintype "unspecified+no_connect"))
    )
    (net (code "56") (name "unconnected-(U11-PA9-Pad42)") (class "Default")
      (node (ref "U11") (pin "42") (pinfunction "PA9_42") (pintype "unspecified+no_connect"))
    )
    (net (code "57") (name "unconnected-(U11-PA10-Pad43)") (class "Default")
      (node (ref "U11") (pin "43") (pinfunction "PA10_43") (pintype "unspecified+no_connect"))
    )
    (net (code "58") (name "unconnected-(U11-PA15-Pad50)") (class "Default")
      (node (ref "U11") (pin "50") (pinfunction "PA15_50") (pintype "unspecified+no_connect"))
    )
    (net (code "59") (name "unconnected-(U11-PB0-Pad26)") (class "Default")
      (node (ref "U11") (pin "26") (pinfunction "PB0_26") (pintype "unspecified+no_connect"))
    )
    (net (code "60") (name "unconnected-(U11-PB1-Pad27)") (class "Default")
      (node (ref "U11") (pin "27") (pinfunction "PB1_27") (pintype "unspecified+no_connect"))
    )
    (net (code "61") (name "unconnected-(U11-PB2-Pad28)") (class "Default")
      (node (ref "U11") (pin "28") (pinfunction "PB2_28") (pintype "unspecified+no_connect"))
    )
    (net (code "62") (name "unconnected-(U11-PB3-Pad55)") (class "Default")
      (node (ref "U11") (pin "55") (pinfunction "PB3_55") (pintype "unspecified+no_connect"))
    )
    (net (code "63") (name "unconnected-(U11-PB4-Pad56)") (class "Default")
      (node (ref "U11") (pin "56") (pinfunction "PB4_56") (pintype "unspecified+no_connect"))
    )
    (net (code "64") (name "unconnected-(U11-PB5-Pad57)") (class "Default")
      (node (ref "U11") (pin "57") (pinfunction "PB5_57") (pintype "unspecified+no_connect"))
    )
    (net (code "65") (name "unconnected-(U11-PB10-Pad29)") (class "Default")
      (node (ref "U11") (pin "29") (pinfunction "PB10_29") (pintype "unspecified+no_connect"))
    )
    (net (code "66") (name "unconnected-(U11-PB11-Pad30)") (class "Default")
      (node (ref "U11") (pin "30") (pinfunction "PB11_30") (pintype "unspecified+no_connect"))
    )
    (net (code "67") (name "unconnected-(U11-PB12-Pad33)") (class "Default")
      (node (ref "U11") (pin "33") (pinfunction "PB12_33") (pintype "unspecified+no_connect"))
    )
    (net (code "68") (name "unconnected-(U11-PB13-Pad34)") (class "Default")
      (node (ref "U11") (pin "34") (pinfunction "PB13_34") (pintype "unspecified+no_connect"))
    )
    (net (code "69") (name "unconnected-(U11-PB14-Pad35)") (class "Default")
      (node (ref "U11") (pin "35") (pinfunction "PB14_35") (pintype "unspecified+no_connect"))
    )
    (net (code "70") (name "unconnected-(U11-PB15-Pad36)") (class "Default")
      (node (ref "U11") (pin "36") (pinfunction "PB15_36") (pintype "unspecified+no_connect"))
    )
    (net (code "71") (name "unconnected-(U11-PC0-Pad8)") (class "Default")
      (node (ref "U11") (pin "8") (pinfunction "PC0_8") (pintype "unspecified+no_connect"))
    )
    (net (code "72") (name "unconnected-(U11-PC1-Pad9)") (class "Default")
      (node (ref "U11") (pin "9") (pinfunction "PC1_9") (pintype "unspecified+no_connect"))
    )
    (net (code "73") (name "unconnected-(U11-PC2-Pad10)") (class "Default")
      (node (ref "U11") (pin "10") (pinfunction "PC2_10") (pintype "unspecified+no_connect"))
    )
    (net (code "74") (name "unconnected-(U11-PC3-Pad11)") (class "Default")
      (node (ref "U11") (pin "11") (pinfunction "PC3_11") (pintype "unspecified+no_connect"))
    )
    (net (code "75") (name "unconnected-(U11-PC4-Pad24)") (class "Default")
      (node (ref "U11") (pin "24") (pinfunction "PC4_24") (pintype "unspecified+no_connect"))
    )
    (net (code "76") (name "unconnected-(U11-PC5-Pad25)") (class "Default")
      (node (ref "U11") (pin "25") (pinfunction "PC5_25") (pintype "unspecified+no_connect"))
    )
    (net (code "77") (name "unconnected-(U11-PC10-Pad51)") (class "Default")
      (node (ref "U11") (pin "51") (pinfunction "PC10_51") (pintype "unspecified+no_connect"))
    )
    (net (code "78") (name "unconnected-(U11-PC11-Pad52)") (class "Default")
      (node (ref "U11") (pin "52") (pinfunction "PC11_52") (pintype "unspecified+no_connect"))
    )
    (net (code "79") (name "unconnected-(U11-PC12-Pad53)") (class "Default")
      (node (ref "U11") (pin "53") (pinfunction "PC12_53") (pintype "unspecified+no_connect"))
    )
    (net (code "80") (name "unconnected-(U11-PC15-OSC32_OUT-Pad4)") (class "Default")
      (node (ref "U11") (pin "4") (pinfunction "PC15-OSC32_OUT_4") (pintype "unspecified+no_connect"))
    )
    (net (code "81") (name "unconnected-(U11-PD2-Pad54)") (class "Default")
      (node (ref "U11") (pin "54") (pinfunction "PD2_54") (pintype "unspecified+no_connect"))
    )
    (net (code "82") (name "unconnected-(U11-VDDA-Pad13)") (class "Default")
      (node (ref "U11") (pin "13") (pinfunction "VDDA_13") (pintype "unspecified+no_connect"))
    )
    (net (code "83") (name "unconnected-(U11-VSSA-Pad12)") (class "Default")
      (node (ref "U11") (pin "12") (pinfunction "VSSA_12") (pintype "unspecified+no_connect"))
    )
    (net (code "84") (name "unconnected-(U21-N.C.-Pad7)") (class "Default")
      (node (ref "U21") (pin "7") (pinfunction "N.C._7") (pintype "unspecified"))
    )
    (net (code "85") (name "unconnected-(YAW-Pad6)") (class "Default")
      (node (ref "YAW") (pin "6") (pinfunction "6_6") (pintype "unspecified+no_connect"))
    )
    (net (code "86") (name "unconnected-(YAW-Pad7)") (class "Default")
      (node (ref "YAW") (pin "7") (pinfunction "7_7") (pintype "unspecified+no_connect"))
    )
  )
)
